# MCU.net
KiCad netlist of a schematic drawn in Altium Designer
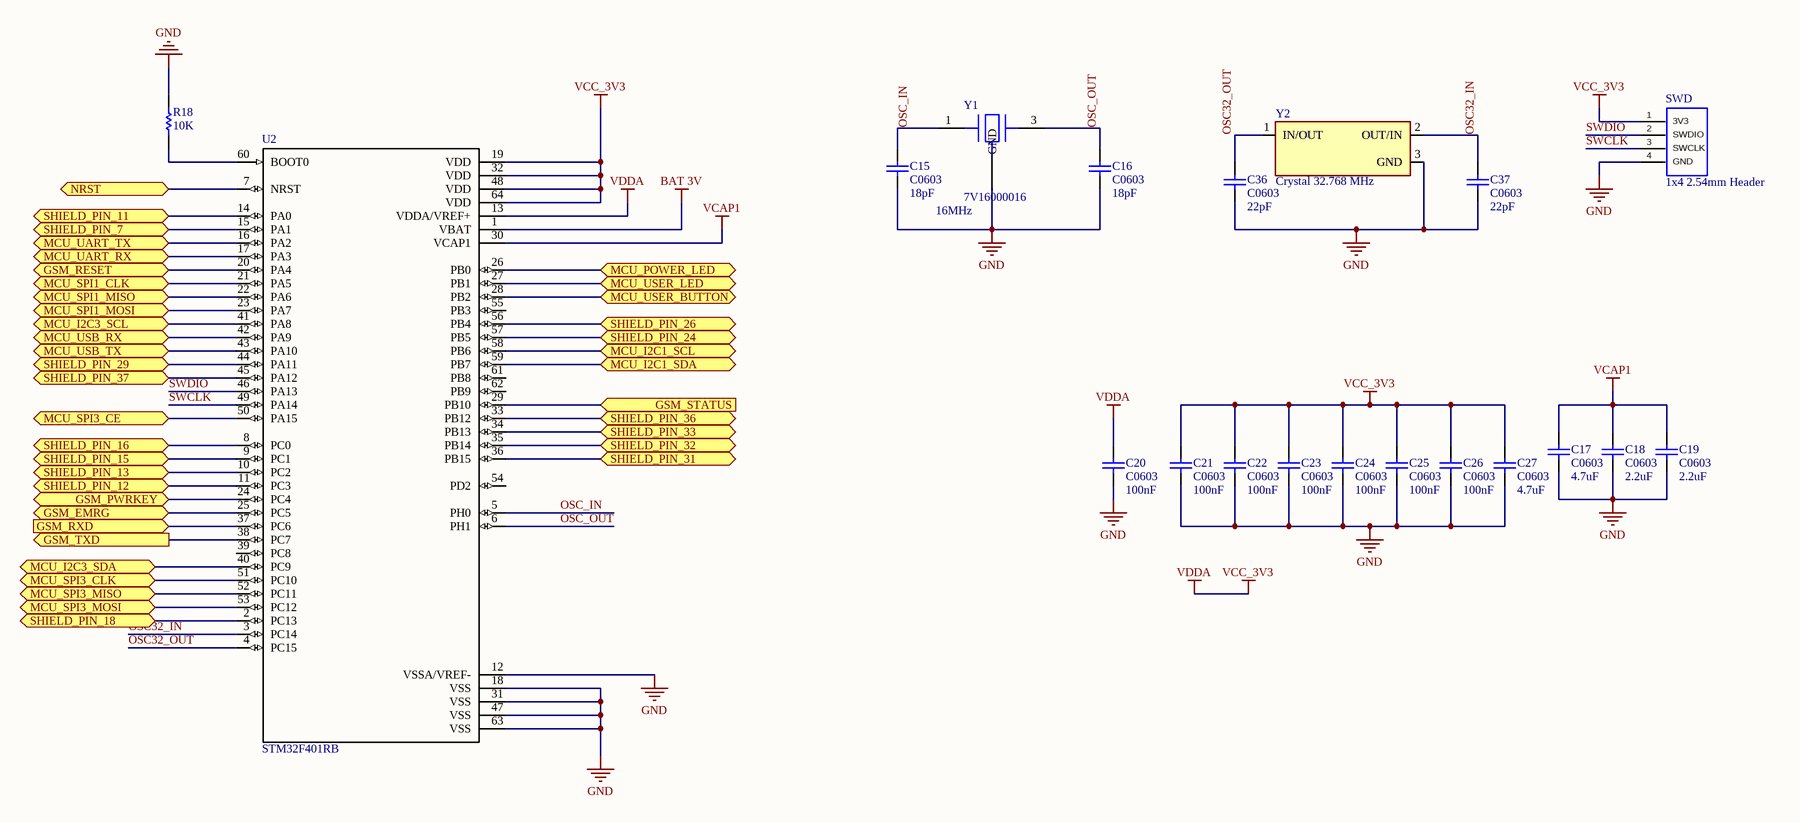
[diagram p0: MCU.SchDoc]

(export (version "E")
  (design (tool "Eeschema 10.0.6"))
  (components
    (comp (ref "C15")
      (value "C0603")
      (footprint "C0603")
      (description "Ceramic Chip Capacitor - Standard")
      (fields (field (name "ALTIUM_VALUE") "18pF") (field (name "PUBLISHER") "Altium Limited"))
      (libsource (lib "haberlesme") (part "C0603"))
    )
    (comp (ref "C16")
      (value "C0603")
      (footprint "C0603")
      (description "Ceramic Chip Capacitor - Standard")
      (fields (field (name "ALTIUM_VALUE") "18pF") (field (name "PUBLISHER") "Altium Limited"))
      (libsource (lib "haberlesme") (part "C0603"))
    )
    (comp (ref "C17")
      (value "C0603")
      (footprint "C0603")
      (description "Ceramic Chip Capacitor - Standard")
      (fields (field (name "ALTIUM_VALUE") "4.7uF") (field (name "PUBLISHER") "Altium Limited"))
      (libsource (lib "haberlesme") (part "C0603"))
    )
    (comp (ref "C18")
      (value "C0603")
      (footprint "C0603")
      (description "Ceramic Chip Capacitor - Standard")
      (fields (field (name "ALTIUM_VALUE") "2.2uF") (field (name "PUBLISHER") "Altium Limited"))
      (libsource (lib "haberlesme") (part "C0603"))
    )
    (comp (ref "C19")
      (value "C0603")
      (footprint "C0603")
      (description "Ceramic Chip Capacitor - Standard")
      (fields (field (name "ALTIUM_VALUE") "2.2uF") (field (name "PUBLISHER") "Altium Limited"))
      (libsource (lib "haberlesme") (part "C0603"))
    )
    (comp (ref "C20")
      (value "C0603")
      (footprint "C0603")
      (description "Ceramic Chip Capacitor - Standard")
      (fields (field (name "ALTIUM_VALUE") "100nF") (field (name "PUBLISHER") "Altium Limited"))
      (libsource (lib "haberlesme") (part "C0603"))
    )
    (comp (ref "C21")
      (value "C0603")
      (footprint "C0603")
      (description "Ceramic Chip Capacitor - Standard")
      (fields (field (name "ALTIUM_VALUE") "100nF") (field (name "PUBLISHER") "Altium Limited"))
      (libsource (lib "haberlesme") (part "C0603"))
    )
    (comp (ref "C22")
      (value "C0603")
      (footprint "C0603")
      (description "Ceramic Chip Capacitor - Standard")
      (fields (field (name "ALTIUM_VALUE") "100nF") (field (name "PUBLISHER") "Altium Limited"))
      (libsource (lib "haberlesme") (part "C0603"))
    )
    (comp (ref "C23")
      (value "C0603")
      (footprint "C0603")
      (description "Ceramic Chip Capacitor - Standard")
      (fields (field (name "ALTIUM_VALUE") "100nF") (field (name "PUBLISHER") "Altium Limited"))
      (libsource (lib "haberlesme") (part "C0603"))
    )
    (comp (ref "C24")
      (value "C0603")
      (footprint "C0603")
      (description "Ceramic Chip Capacitor - Standard")
      (fields (field (name "ALTIUM_VALUE") "100nF") (field (name "PUBLISHER") "Altium Limited"))
      (libsource (lib "haberlesme") (part "C0603"))
    )
    (comp (ref "C25")
      (value "C0603")
      (footprint "C0603")
      (description "Ceramic Chip Capacitor - Standard")
      (fields (field (name "ALTIUM_VALUE") "100nF") (field (name "PUBLISHER") "Altium Limited"))
      (libsource (lib "haberlesme") (part "C0603"))
    )
    (comp (ref "C26")
      (value "C0603")
      (footprint "C0603")
      (description "Ceramic Chip Capacitor - Standard")
      (fields (field (name "ALTIUM_VALUE") "100nF") (field (name "PUBLISHER") "Altium Limited"))
      (libsource (lib "haberlesme") (part "C0603"))
    )
    (comp (ref "C27")
      (value "C0603")
      (footprint "C0603")
      (description "Ceramic Chip Capacitor - Standard")
      (fields (field (name "ALTIUM_VALUE") "4.7uF") (field (name "PUBLISHER") "Altium Limited"))
      (libsource (lib "haberlesme") (part "C0603"))
    )
    (comp (ref "C36")
      (value "C0603")
      (footprint "C0603")
      (description "Ceramic Chip Capacitor - Standard")
      (fields (field (name "ALTIUM_VALUE") "22pF") (field (name "PUBLISHER") "Altium Limited"))
      (libsource (lib "haberlesme") (part "C0603"))
    )
    (comp (ref "C37")
      (value "C0603")
      (footprint "C0603")
      (description "Ceramic Chip Capacitor - Standard")
      (fields (field (name "ALTIUM_VALUE") "22pF") (field (name "PUBLISHER") "Altium Limited"))
      (libsource (lib "haberlesme") (part "C0603"))
    )
    (comp (ref "R18")
      (value "10K")
      (footprint "Isbak:CC1608-0603")
      (description "Resistor")
      (fields
        (field (name "MANUFACTURER") "Generic Components")
        (field (name "Comment") "Res0603")
        (field (name "PUBLISHER") "Altium Limited")
      )
      (libsource (lib "Isbak") (part "Res0603"))
    )
    (comp (ref "SWD")
      (value "1x4 2.54mm Header")
      (footprint "1x4 2.54mm Header")
      (libsource (lib "haberlesme") (part "1x4 2.54mm Header"))
    )
    (comp (ref "U2")
      (value "STM32F401RB")
      (footprint "STM32F401RE")
      (libsource (lib "haberlesme") (part "STM32F401RE"))
    )
    (comp (ref "Y1")
      (value "7V16000016")
      (footprint "7V16000016")
      (fields (field (name "ALTIUM_VALUE") "16MHz"))
      (libsource (lib "haberlesme") (part "7V16000016"))
    )
    (comp (ref "Y2")
      (value "Crystal 32.768 MHz")
      (footprint "Crystal 32.768 MHz")
      (libsource (lib "haberlesme") (part "Crystal 32.768 MHz"))
    )
  )
  (nets
    (net (code "1") (name "/GSM_EMRG") (class "Default")
      (node (ref "U2") (pin "25") (pinfunction "PC5_25") (pintype "bidirectional"))
    )
    (net (code "2") (name "/GSM_PWRKEY") (class "Default")
      (node (ref "U2") (pin "24") (pinfunction "PC4_24") (pintype "bidirectional"))
    )
    (net (code "3") (name "/GSM_RESET") (class "Default")
      (node (ref "U2") (pin "20") (pinfunction "PA4_20") (pintype "bidirectional"))
    )
    (net (code "4") (name "/GSM_RXD") (class "Default")
      (node (ref "U2") (pin "37") (pinfunction "PC6_37") (pintype "bidirectional"))
    )
    (net (code "5") (name "/GSM_STATUS") (class "Default")
      (node (ref "U2") (pin "29") (pinfunction "PB10_29") (pintype "bidirectional"))
    )
    (net (code "6") (name "/GSM_TXD") (class "Default")
      (node (ref "U2") (pin "38") (pinfunction "PC7_38") (pintype "bidirectional"))
    )
    (net (code "7") (name "/MCU_I2C1_SCL") (class "Default")
      (node (ref "U2") (pin "58") (pinfunction "PB6_58") (pintype "bidirectional"))
    )
    (net (code "8") (name "/MCU_I2C1_SDA") (class "Default")
      (node (ref "U2") (pin "59") (pinfunction "PB7_59") (pintype "bidirectional"))
    )
    (net (code "9") (name "/MCU_I2C3_SCL") (class "Default")
      (node (ref "U2") (pin "41") (pinfunction "PA8_41") (pintype "bidirectional"))
    )
    (net (code "10") (name "/MCU_I2C3_SDA") (class "Default")
      (node (ref "U2") (pin "40") (pinfunction "PC9_40") (pintype "bidirectional"))
    )
    (net (code "11") (name "/MCU_POWER_LED") (class "Default")
      (node (ref "U2") (pin "26") (pinfunction "PB0_26") (pintype "bidirectional"))
    )
    (net (code "12") (name "/MCU_SPI1_CLK") (class "Default")
      (node (ref "U2") (pin "21") (pinfunction "PA5_21") (pintype "bidirectional"))
    )
    (net (code "13") (name "/MCU_SPI1_MISO") (class "Default")
      (node (ref "U2") (pin "22") (pinfunction "PA6_22") (pintype "bidirectional"))
    )
    (net (code "14") (name "/MCU_SPI1_MOSI") (class "Default")
      (node (ref "U2") (pin "23") (pinfunction "PA7_23") (pintype "bidirectional"))
    )
    (net (code "15") (name "/MCU_SPI3_CE") (class "Default")
      (node (ref "U2") (pin "50") (pinfunction "PA15_50") (pintype "bidirectional"))
    )
    (net (code "16") (name "/MCU_SPI3_CLK") (class "Default")
      (node (ref "U2") (pin "51") (pinfunction "PC10_51") (pintype "bidirectional"))
    )
    (net (code "17") (name "/MCU_SPI3_MISO") (class "Default")
      (node (ref "U2") (pin "52") (pinfunction "PC11_52") (pintype "bidirectional"))
    )
    (net (code "18") (name "/MCU_SPI3_MOSI") (class "Default")
      (node (ref "U2") (pin "53") (pinfunction "PC12_53") (pintype "bidirectional"))
    )
    (net (code "19") (name "/MCU_UART_RX") (class "Default")
      (node (ref "U2") (pin "17") (pinfunction "PA3_17") (pintype "bidirectional"))
    )
    (net (code "20") (name "/MCU_UART_TX") (class "Default")
      (node (ref "U2") (pin "16") (pinfunction "PA2_16") (pintype "bidirectional"))
    )
    (net (code "21") (name "/MCU_USB_RX") (class "Default")
      (node (ref "U2") (pin "42") (pinfunction "PA9_42") (pintype "bidirectional"))
    )
    (net (code "22") (name "/MCU_USB_TX") (class "Default")
      (node (ref "U2") (pin "43") (pinfunction "PA10_43") (pintype "bidirectional"))
    )
    (net (code "23") (name "/MCU_USER_BUTTON") (class "Default")
      (node (ref "U2") (pin "28") (pinfunction "PB2_28") (pintype "bidirectional"))
    )
    (net (code "24") (name "/MCU_USER_LED") (class "Default")
      (node (ref "U2") (pin "27") (pinfunction "PB1_27") (pintype "bidirectional"))
    )
    (net (code "25") (name "/NRST") (class "Default")
      (node (ref "U2") (pin "7") (pinfunction "NRST_7") (pintype "bidirectional"))
    )
    (net (code "26") (name "/OSC32_IN") (class "Default")
      (node (ref "C37") (pin "1") (pinfunction "1_1") (pintype "passive"))
      (node (ref "U2") (pin "3") (pinfunction "PC14_3") (pintype "bidirectional"))
      (node (ref "Y2") (pin "2") (pinfunction "OUT/IN_2") (pintype "bidirectional"))
    )
    (net (code "27") (name "/OSC32_OUT") (class "Default")
      (node (ref "C36") (pin "1") (pinfunction "1_1") (pintype "passive"))
      (node (ref "U2") (pin "4") (pinfunction "PC15_4") (pintype "bidirectional"))
      (node (ref "Y2") (pin "1") (pinfunction "IN/OUT_1") (pintype "bidirectional"))
    )
    (net (code "28") (name "/OSC_IN") (class "Default")
      (node (ref "C15") (pin "2") (pinfunction "2_2") (pintype "passive"))
      (node (ref "U2") (pin "5") (pinfunction "PH0_5") (pintype "bidirectional"))
      (node (ref "Y1") (pin "1") (pinfunction "1_1") (pintype "passive"))
    )
    (net (code "29") (name "/OSC_OUT") (class "Default")
      (node (ref "C16") (pin "2") (pinfunction "2_2") (pintype "passive"))
      (node (ref "U2") (pin "6") (pinfunction "PH1_6") (pintype "bidirectional"))
      (node (ref "Y1") (pin "3") (pinfunction "3_3") (pintype "passive"))
    )
    (net (code "30") (name "/SHIELD_PIN_7") (class "Default")
      (node (ref "U2") (pin "15") (pinfunction "PA1_15") (pintype "bidirectional"))
    )
    (net (code "31") (name "/SHIELD_PIN_11") (class "Default")
      (node (ref "U2") (pin "14") (pinfunction "PA0_14") (pintype "bidirectional"))
    )
    (net (code "32") (name "/SHIELD_PIN_12") (class "Default")
      (node (ref "U2") (pin "11") (pinfunction "PC3_11") (pintype "bidirectional"))
    )
    (net (code "33") (name "/SHIELD_PIN_13") (class "Default")
      (node (ref "U2") (pin "10") (pinfunction "PC2_10") (pintype "bidirectional"))
    )
    (net (code "34") (name "/SHIELD_PIN_15") (class "Default")
      (node (ref "U2") (pin "9") (pinfunction "PC1_9") (pintype "bidirectional"))
    )
    (net (code "35") (name "/SHIELD_PIN_16") (class "Default")
      (node (ref "U2") (pin "8") (pinfunction "PC0_8") (pintype "bidirectional"))
    )
    (net (code "36") (name "/SHIELD_PIN_18") (class "Default")
      (node (ref "U2") (pin "2") (pinfunction "PC13_2") (pintype "bidirectional"))
    )
    (net (code "37") (name "/SHIELD_PIN_24") (class "Default")
      (node (ref "U2") (pin "57") (pinfunction "PB5_57") (pintype "bidirectional"))
    )
    (net (code "38") (name "/SHIELD_PIN_26") (class "Default")
      (node (ref "U2") (pin "56") (pinfunction "PB4_56") (pintype "bidirectional"))
    )
    (net (code "39") (name "/SHIELD_PIN_29") (class "Default")
      (node (ref "U2") (pin "44") (pinfunction "PA11_44") (pintype "bidirectional"))
    )
    (net (code "40") (name "/SHIELD_PIN_31") (class "Default")
      (node (ref "U2") (pin "36") (pinfunction "PB15_36") (pintype "bidirectional"))
    )
    (net (code "41") (name "/SHIELD_PIN_32") (class "Default")
      (node (ref "U2") (pin "35") (pinfunction "PB14_35") (pintype "bidirectional"))
    )
    (net (code "42") (name "/SHIELD_PIN_33") (class "Default")
      (node (ref "U2") (pin "34") (pinfunction "PB13_34") (pintype "bidirectional"))
    )
    (net (code "43") (name "/SHIELD_PIN_36") (class "Default")
      (node (ref "U2") (pin "33") (pinfunction "PB12_33") (pintype "bidirectional"))
    )
    (net (code "44") (name "/SHIELD_PIN_37") (class "Default")
      (node (ref "U2") (pin "45") (pinfunction "PA12_45") (pintype "bidirectional"))
    )
    (net (code "45") (name "/SWCLK") (class "Default")
      (node (ref "SWD") (pin "3") (pinfunction "SWCLK_3") (pintype "passive"))
      (node (ref "U2") (pin "49") (pinfunction "PA14_49") (pintype "bidirectional"))
    )
    (net (code "46") (name "/SWDIO") (class "Default")
      (node (ref "SWD") (pin "2") (pinfunction "SWDIO_2") (pintype "passive"))
      (node (ref "U2") (pin "46") (pinfunction "PA13_46") (pintype "bidirectional"))
    )
    (net (code "47") (name "BAT 3V") (class "Default")
      (node (ref "U2") (pin "1") (pinfunction "VBAT_1") (pintype "power_in"))
    )
    (net (code "48") (name "GND") (class "Default")
      (node (ref "C15") (pin "1") (pinfunction "1_1") (pintype "passive"))
      (node (ref "C16") (pin "1") (pinfunction "1_1") (pintype "passive"))
      (node (ref "C17") (pin "2") (pinfunction "2_2") (pintype "passive"))
      (node (ref "C18") (pin "2") (pinfunction "2_2") (pintype "passive"))
      (node (ref "C19") (pin "2") (pinfunction "2_2") (pintype "passive"))
      (node (ref "C20") (pin "2") (pinfunction "2_2") (pintype "passive"))
      (node (ref "C21") (pin "1") (pinfunction "1_1") (pintype "passive"))
      (node (ref "C22") (pin "1") (pinfunction "1_1") (pintype "passive"))
      (node (ref "C23") (pin "1") (pinfunction "1_1") (pintype "passive"))
      (node (ref "C24") (pin "1") (pinfunction "1_1") (pintype "passive"))
      (node (ref "C25") (pin "1") (pinfunction "1_1") (pintype "passive"))
      (node (ref "C26") (pin "1") (pinfunction "1_1") (pintype "passive"))
      (node (ref "C27") (pin "1") (pinfunction "1_1") (pintype "passive"))
      (node (ref "C36") (pin "2") (pinfunction "2_2") (pintype "passive"))
      (node (ref "C37") (pin "2") (pinfunction "2_2") (pintype "passive"))
      (node (ref "R18") (pin "1") (pinfunction "1_1") (pintype "passive"))
      (node (ref "SWD") (pin "4") (pinfunction "GND_4") (pintype "passive"))
      (node (ref "U2") (pin "12") (pinfunction "VSSA/VREF-_12") (pintype "power_in"))
      (node (ref "U2") (pin "18") (pinfunction "VSS_18") (pintype "power_in"))
      (node (ref "U2") (pin "31") (pinfunction "VSS_31") (pintype "power_in"))
      (node (ref "U2") (pin "47") (pinfunction "VSS_47") (pintype "power_in"))
      (node (ref "U2") (pin "63") (pinfunction "VSS_63") (pintype "power_in"))
      (node (ref "Y1") (pin "2") (pinfunction "GND_2") (pintype "passive"))
      (node (ref "Y2") (pin "3") (pinfunction "GND_3") (pintype "power_in"))
    )
    (net (code "49") (name "Net-(U2-BOOT0)") (class "Default")
      (node (ref "R18") (pin "2") (pinfunction "2_2") (pintype "passive"))
      (node (ref "U2") (pin "60") (pinfunction "BOOT0_60") (pintype "input"))
    )
    (net (code "50") (name "VCAP1") (class "Default")
      (node (ref "C17") (pin "1") (pinfunction "1_1") (pintype "passive"))
      (node (ref "C18") (pin "1") (pinfunction "1_1") (pintype "passive"))
      (node (ref "C19") (pin "1") (pinfunction "1_1") (pintype "passive"))
      (node (ref "U2") (pin "30") (pinfunction "VCAP1_30") (pintype "power_in"))
    )
    (net (code "51") (name "VCC_3V3") (class "Default")
      (node (ref "C20") (pin "1") (pinfunction "1_1") (pintype "passive"))
      (node (ref "C21") (pin "2") (pinfunction "2_2") (pintype "passive"))
      (node (ref "C22") (pin "2") (pinfunction "2_2") (pintype "passive"))
      (node (ref "C23") (pin "2") (pinfunction "2_2") (pintype "passive"))
      (node (ref "C24") (pin "2") (pinfunction "2_2") (pintype "passive"))
      (node (ref "C25") (pin "2") (pinfunction "2_2") (pintype "passive"))
      (node (ref "C26") (pin "2") (pinfunction "2_2") (pintype "passive"))
      (node (ref "C27") (pin "2") (pinfunction "2_2") (pintype "passive"))
      (node (ref "SWD") (pin "1") (pinfunction "3V3_1") (pintype "passive"))
      (node (ref "U2") (pin "13") (pinfunction "VDDA/VREF+_13") (pintype "power_in"))
      (node (ref "U2") (pin "19") (pinfunction "VDD_19") (pintype "power_in"))
      (node (ref "U2") (pin "32") (pinfunction "VDD_32") (pintype "power_in"))
      (node (ref "U2") (pin "48") (pinfunction "VDD_48") (pintype "power_in"))
      (node (ref "U2") (pin "64") (pinfunction "VDD_64") (pintype "power_in"))
    )
    (net (code "52") (name "unconnected-(U2-PB3-Pad55)") (class "Default")
      (node (ref "U2") (pin "55") (pinfunction "PB3_55") (pintype "bidirectional"))
    )
    (net (code "53") (name "unconnected-(U2-PB8-Pad61)") (class "Default")
      (node (ref "U2") (pin "61") (pinfunction "PB8_61") (pintype "bidirectional"))
    )
    (net (code "54") (name "unconnected-(U2-PB9-Pad62)") (class "Default")
      (node (ref "U2") (pin "62") (pinfunction "PB9_62") (pintype "bidirectional"))
    )
    (net (code "55") (name "unconnected-(U2-PC8-Pad39)") (class "Default")
      (node (ref "U2") (pin "39") (pinfunction "PC8_39") (pintype "bidirectional"))
    )
    (net (code "56") (name "unconnected-(U2-PD2-Pad54)") (class "Default")
      (node (ref "U2") (pin "54") (pinfunction "PD2_54") (pintype "bidirectional"))
    )
    (net (code "57") (name "unconnected-(Y1-GND-Pad4)") (class "Default")
      (node (ref "Y1") (pin "4") (pinfunction "GND_4") (pintype "passive"))
      (node (ref "Y1") (pin "1") (pinfunction "GND_1") (pintype "passive"))
    )
  )
)
